# teleinfokit.net
KiCad netlist of a schematic drawn in EAGLE
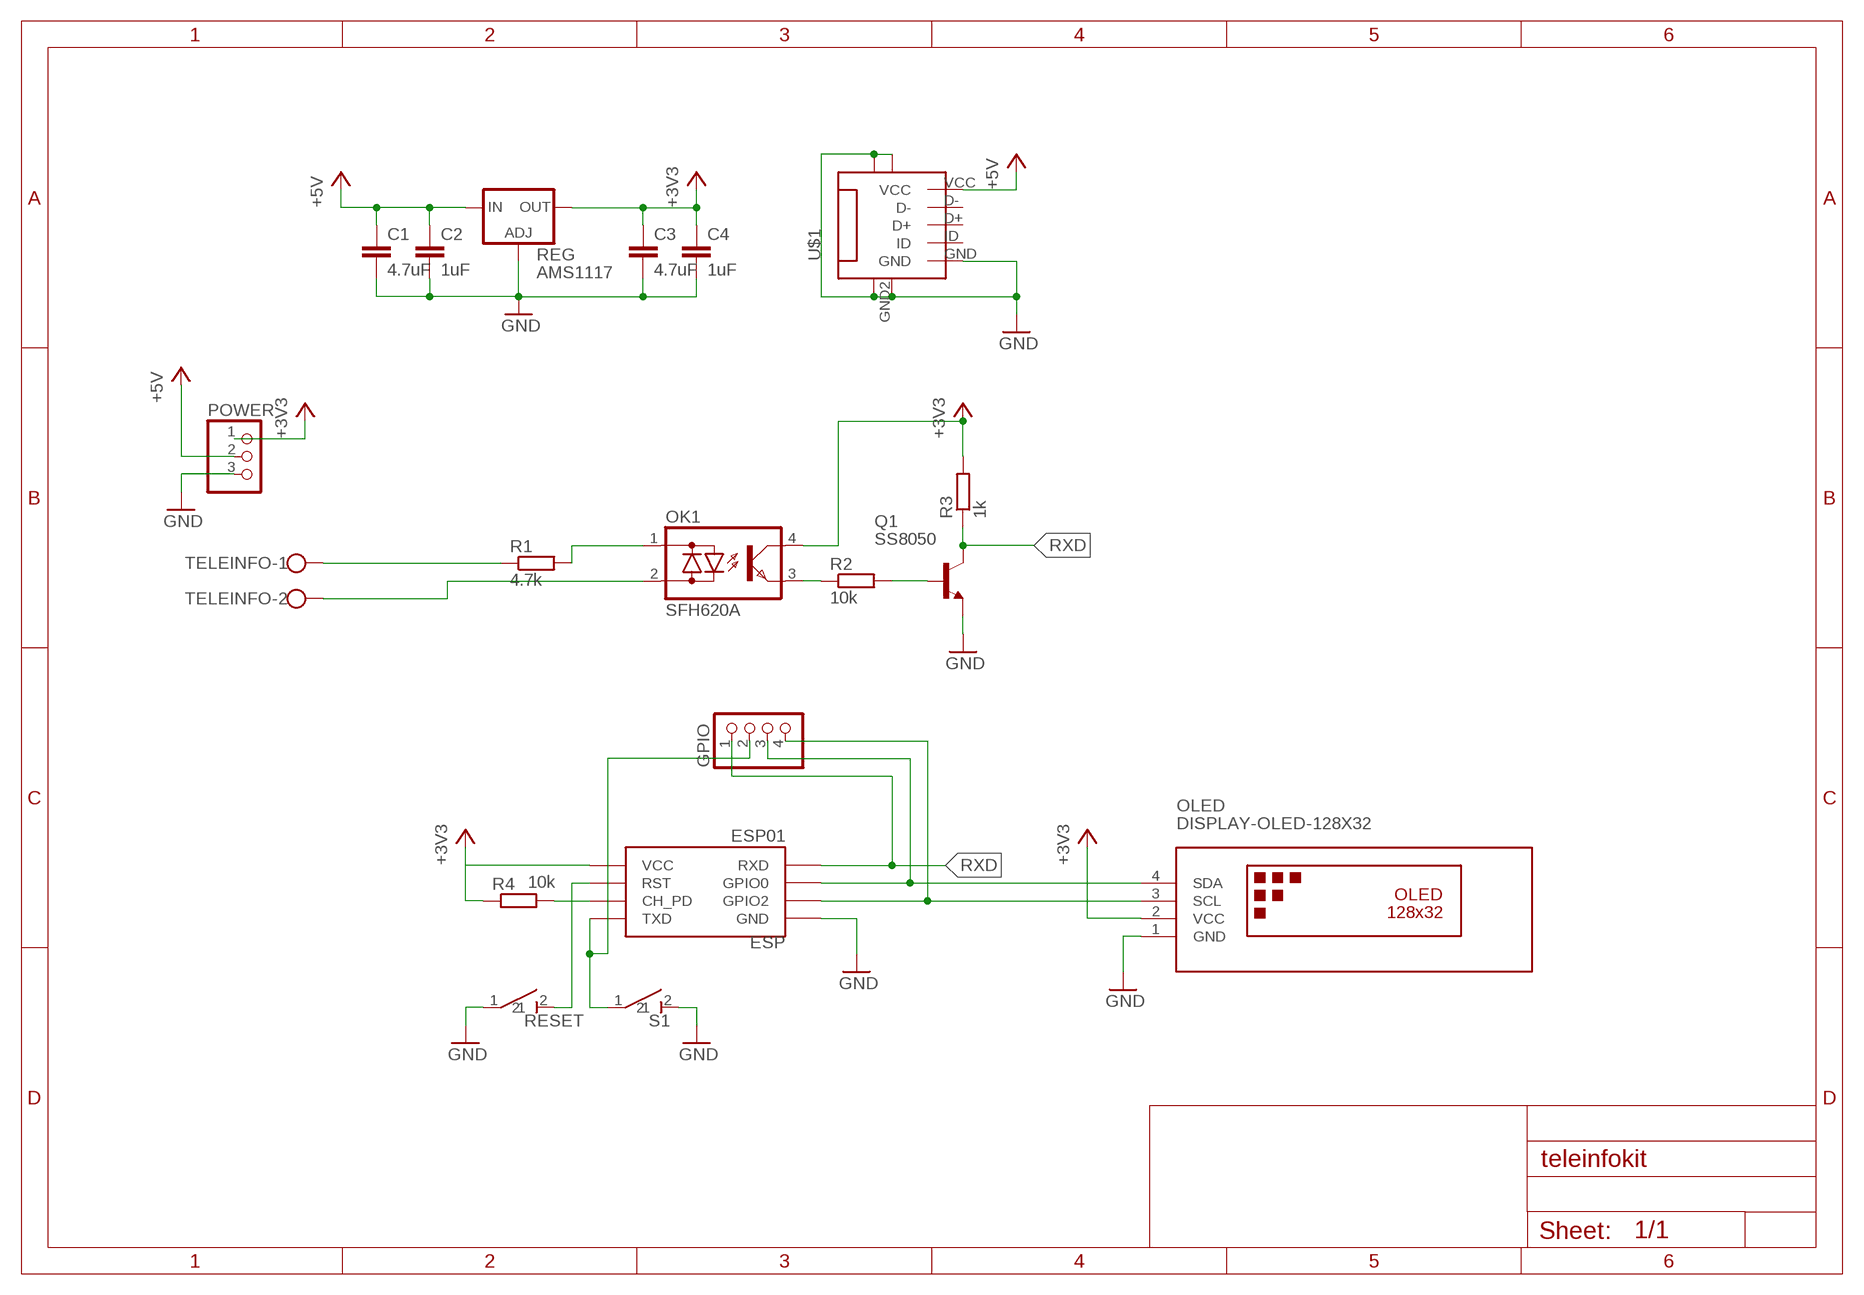
[diagram p0: schematic, sheet 1]

(export (version "E")
  (design (tool "Eeschema 10.0.6"))
  (components
    (comp (ref "C1")
      (value "4.7uF")
      (footprint "eagle-import:C0805")
      (fields (field (name "LCSC_PART") "C1779"))
      (libsource (lib "eagle-import") (part "C-EUC0805"))
    )
    (comp (ref "C2")
      (value "1uF")
      (footprint "eagle-import:C0805")
      (fields (field (name "LCSC_PART") "C28323"))
      (libsource (lib "eagle-import") (part "C-EUC0805"))
    )
    (comp (ref "C3")
      (value "4.7uF")
      (footprint "eagle-import:C0805")
      (fields (field (name "LCSC_PART") "C1779"))
      (libsource (lib "eagle-import") (part "C-EUC0805"))
    )
    (comp (ref "C4")
      (value "1uF")
      (footprint "eagle-import:C0805")
      (fields (field (name "LCSC_PART") "C28323"))
      (libsource (lib "eagle-import") (part "C-EUC0805"))
    )
    (comp (ref "ESP")
      (value "ESP01")
      (footprint "eagle-import:ESP01")
      (libsource (lib "eagle-import") (part "ESP01"))
    )
    (comp (ref "GPIO")
      (value "PINHD-1X4")
      (footprint "eagle-import:1X04")
      (libsource (lib "eagle-import") (part "PINHD-1X4"))
    )
    (comp (ref "OK1")
      (value "SFH620A")
      (footprint "eagle-import:DIL04")
      (fields (field (name "MPN") "SFH620A-2"))
      (libsource (lib "eagle-import") (part "SFH620A"))
    )
    (comp (ref "OLED")
      (value "DISPLAY-OLED-128X32")
      (footprint "eagle-import:DISPLAY-OLED-128X32")
      (libsource (lib "eagle-import") (part "DISPLAY-OLED-128X32"))
    )
    (comp (ref "POWER")
      (value "PINHD-1X3")
      (footprint "eagle-import:1X03")
      (libsource (lib "eagle-import") (part "PINHD-1X3"))
    )
    (comp (ref "Q1")
      (value "SS8050")
      (footprint "eagle-import:SOT23-BEC")
      (fields (field (name "LCSC_PART") "C2150"))
      (libsource (lib "eagle-import") (part "BC850SMD"))
    )
    (comp (ref "R1")
      (value "4.7k")
      (footprint "eagle-import:R0805")
      (fields (field (name "LCSC_PART") "C17673"))
      (libsource (lib "eagle-import") (part "R-EU_R0805"))
    )
    (comp (ref "R2")
      (value "10k")
      (footprint "eagle-import:R0805")
      (fields (field (name "LCSC_PART") "C17414"))
      (libsource (lib "eagle-import") (part "R-EU_R0805"))
    )
    (comp (ref "R3")
      (value "1k")
      (footprint "eagle-import:R0805")
      (fields (field (name "LCSC_PART") "C17513"))
      (libsource (lib "eagle-import") (part "R-EU_R0805"))
    )
    (comp (ref "R4")
      (value "10k")
      (footprint "eagle-import:R0805")
      (fields (field (name "LCSC_PART") "C17414"))
      (libsource (lib "eagle-import") (part "R-EU_R0805"))
    )
    (comp (ref "REG")
      (value "AMS1117")
      (footprint "eagle-import:SOT223")
      (fields (field (name "LCSC_PART") "C6186"))
      (libsource (lib "eagle-import") (part "LD117A?S33TR"))
    )
    (comp (ref "RESET")
      (value "MICROSWITCH")
      (footprint "eagle-import:MICROSWITCH")
      (libsource (lib "eagle-import") (part "MICROSWITCH"))
    )
    (comp (ref "S1")
      (value "MICROSWITCH")
      (footprint "eagle-import:MICROSWITCH")
      (libsource (lib "eagle-import") (part "MICROSWITCH"))
    )
    (comp (ref "TELEINFO")
      (value "W237-102")
      (footprint "eagle-import:W237-102")
      (fields (field (name "MPN") "237-102"))
      (libsource (lib "eagle-import") (part "W237-102"))
    )
    (comp (ref "U$1")
      (value "USB_MICRO_SMD")
      (footprint "eagle-import:USB_MICRO_SMD")
      (fields (field (name "LCSC_PART") "C145783"))
      (libsource (lib "eagle-import") (part "USB_MICRO_SMD"))
    )
  )
  (nets
    (net (code "1") (name "+3V3") (class "Default")
      (node (ref "C3") (pin "1") (pinfunction "1_1") (pintype "passive"))
      (node (ref "C4") (pin "1") (pinfunction "1_1") (pintype "passive"))
      (node (ref "ESP") (pin "VCC") (pinfunction "VCC_VCC") (pintype "bidirectional"))
      (node (ref "OK1") (pin "4") (pinfunction "C_4") (pintype "passive"))
      (node (ref "OLED") (pin "2") (pinfunction "VCC_2") (pintype "power_in"))
      (node (ref "POWER") (pin "1") (pinfunction "1_1") (pintype "passive"))
      (node (ref "R3") (pin "2") (pinfunction "2_2") (pintype "passive"))
      (node (ref "R4") (pin "1") (pinfunction "1_1") (pintype "passive"))
      (node (ref "REG") (pin "4") (pinfunction "OUT_4") (pintype "passive"))
    )
    (net (code "2") (name "+5V") (class "Default")
      (node (ref "C1") (pin "1") (pinfunction "1_1") (pintype "passive"))
      (node (ref "C2") (pin "1") (pinfunction "1_1") (pintype "passive"))
      (node (ref "POWER") (pin "2") (pinfunction "2_2") (pintype "passive"))
      (node (ref "REG") (pin "3") (pinfunction "IN_3") (pintype "input"))
      (node (ref "U$1") (pin "VCC") (pinfunction "VCC_VCC") (pintype "bidirectional"))
    )
    (net (code "3") (name "GND") (class "Default")
      (node (ref "C1") (pin "2") (pinfunction "2_2") (pintype "passive"))
      (node (ref "C2") (pin "2") (pinfunction "2_2") (pintype "passive"))
      (node (ref "C3") (pin "2") (pinfunction "2_2") (pintype "passive"))
      (node (ref "C4") (pin "2") (pinfunction "2_2") (pintype "passive"))
      (node (ref "ESP") (pin "GND") (pinfunction "GND_GND") (pintype "bidirectional"))
      (node (ref "OLED") (pin "1") (pinfunction "GND_1") (pintype "power_in"))
      (node (ref "POWER") (pin "3") (pinfunction "3_3") (pintype "passive"))
      (node (ref "Q1") (pin "E") (pinfunction "E_E") (pintype "passive"))
      (node (ref "REG") (pin "1") (pinfunction "ADJ_1") (pintype "input"))
      (node (ref "RESET") (pin "1") (pinfunction "1_1") (pintype "bidirectional"))
      (node (ref "S1") (pin "2") (pinfunction "2_2") (pintype "bidirectional"))
      (node (ref "U$1") (pin "GND") (pinfunction "GND_GND") (pintype "bidirectional"))
      (node (ref "U$1") (pin "GND1") (pinfunction "GND1_GND1") (pintype "bidirectional"))
      (node (ref "U$1") (pin "GND2") (pinfunction "GND2_GND2") (pintype "bidirectional"))
      (node (ref "U$1") (pin "GND3") (pinfunction "GND3_GND3") (pintype "bidirectional"))
      (node (ref "U$1") (pin "GND4") (pinfunction "GND4_GND4") (pintype "bidirectional"))
    )
    (net (code "4") (name "Net-(ESP-PadCH_PD)") (class "Default")
      (node (ref "ESP") (pin "CH_PD") (pinfunction "CH_PD_CH_PD") (pintype "bidirectional"))
      (node (ref "R4") (pin "2") (pinfunction "2_2") (pintype "passive"))
    )
    (net (code "5") (name "Net-(ESP-PadRST)") (class "Default")
      (node (ref "ESP") (pin "RST") (pinfunction "RST_RST") (pintype "bidirectional"))
      (node (ref "RESET") (pin "2") (pinfunction "2_2") (pintype "bidirectional"))
    )
    (net (code "6") (name "Net-(ESP-TXD)") (class "Default")
      (node (ref "ESP") (pin "TX") (pinfunction "TXD_TX") (pintype "bidirectional"))
      (node (ref "GPIO") (pin "2") (pinfunction "2_2") (pintype "passive"))
      (node (ref "S1") (pin "1") (pinfunction "1_1") (pintype "bidirectional"))
    )
    (net (code "7") (name "Net-(OK1-AC1)") (class "Default")
      (node (ref "OK1") (pin "1") (pinfunction "AC1_1") (pintype "passive"))
      (node (ref "R1") (pin "2") (pinfunction "2_2") (pintype "passive"))
    )
    (net (code "8") (name "Net-(OK1-AC2)") (class "Default")
      (node (ref "OK1") (pin "2") (pinfunction "AC2_2") (pintype "passive"))
      (node (ref "TELEINFO") (pin "2") (pinfunction "KL_2") (pintype "passive"))
    )
    (net (code "9") (name "Net-(OK1-E)") (class "Default")
      (node (ref "OK1") (pin "3") (pinfunction "E_3") (pintype "passive"))
      (node (ref "R2") (pin "1") (pinfunction "1_1") (pintype "passive"))
    )
    (net (code "10") (name "Net-(OLED-SCL)") (class "Default")
      (node (ref "ESP") (pin "GPIO2") (pinfunction "GPIO2_GPIO2") (pintype "bidirectional"))
      (node (ref "GPIO") (pin "4") (pinfunction "4_4") (pintype "passive"))
      (node (ref "OLED") (pin "3") (pinfunction "SCL_3") (pintype "bidirectional"))
    )
    (net (code "11") (name "Net-(OLED-SDA)") (class "Default")
      (node (ref "ESP") (pin "GPIO0") (pinfunction "GPIO0_GPIO0") (pintype "bidirectional"))
      (node (ref "GPIO") (pin "3") (pinfunction "3_3") (pintype "passive"))
      (node (ref "OLED") (pin "4") (pinfunction "SDA_4") (pintype "bidirectional"))
    )
    (net (code "12") (name "Net-(Q1-PadB)") (class "Default")
      (node (ref "Q1") (pin "B") (pinfunction "B_B") (pintype "passive"))
      (node (ref "R2") (pin "2") (pinfunction "2_2") (pintype "passive"))
    )
    (net (code "13") (name "Net-(TELEINFOA-KL)") (class "Default")
      (node (ref "R1") (pin "1") (pinfunction "1_1") (pintype "passive"))
      (node (ref "TELEINFO") (pin "1") (pinfunction "KL_1") (pintype "passive"))
    )
    (net (code "14") (name "RXD") (class "Default")
      (node (ref "ESP") (pin "RX") (pinfunction "RXD_RX") (pintype "bidirectional"))
      (node (ref "GPIO") (pin "1") (pinfunction "1_1") (pintype "passive"))
      (node (ref "Q1") (pin "C") (pinfunction "C_C") (pintype "passive"))
      (node (ref "R3") (pin "1") (pinfunction "1_1") (pintype "passive"))
    )
    (net (code "15") (name "unconnected-(U$1-PadD+)") (class "Default")
      (node (ref "U$1") (pin "D+") (pinfunction "D+_D+") (pintype "bidirectional"))
    )
    (net (code "16") (name "unconnected-(U$1-PadD-)") (class "Default")
      (node (ref "U$1") (pin "D-") (pinfunction "D-_D-") (pintype "bidirectional"))
    )
    (net (code "17") (name "unconnected-(U$1-PadID)") (class "Default")
      (node (ref "U$1") (pin "ID") (pinfunction "ID_ID") (pintype "bidirectional"))
    )
  )
)
